# CutDown2.net
KiCad netlist of a schematic drawn in EAGLE
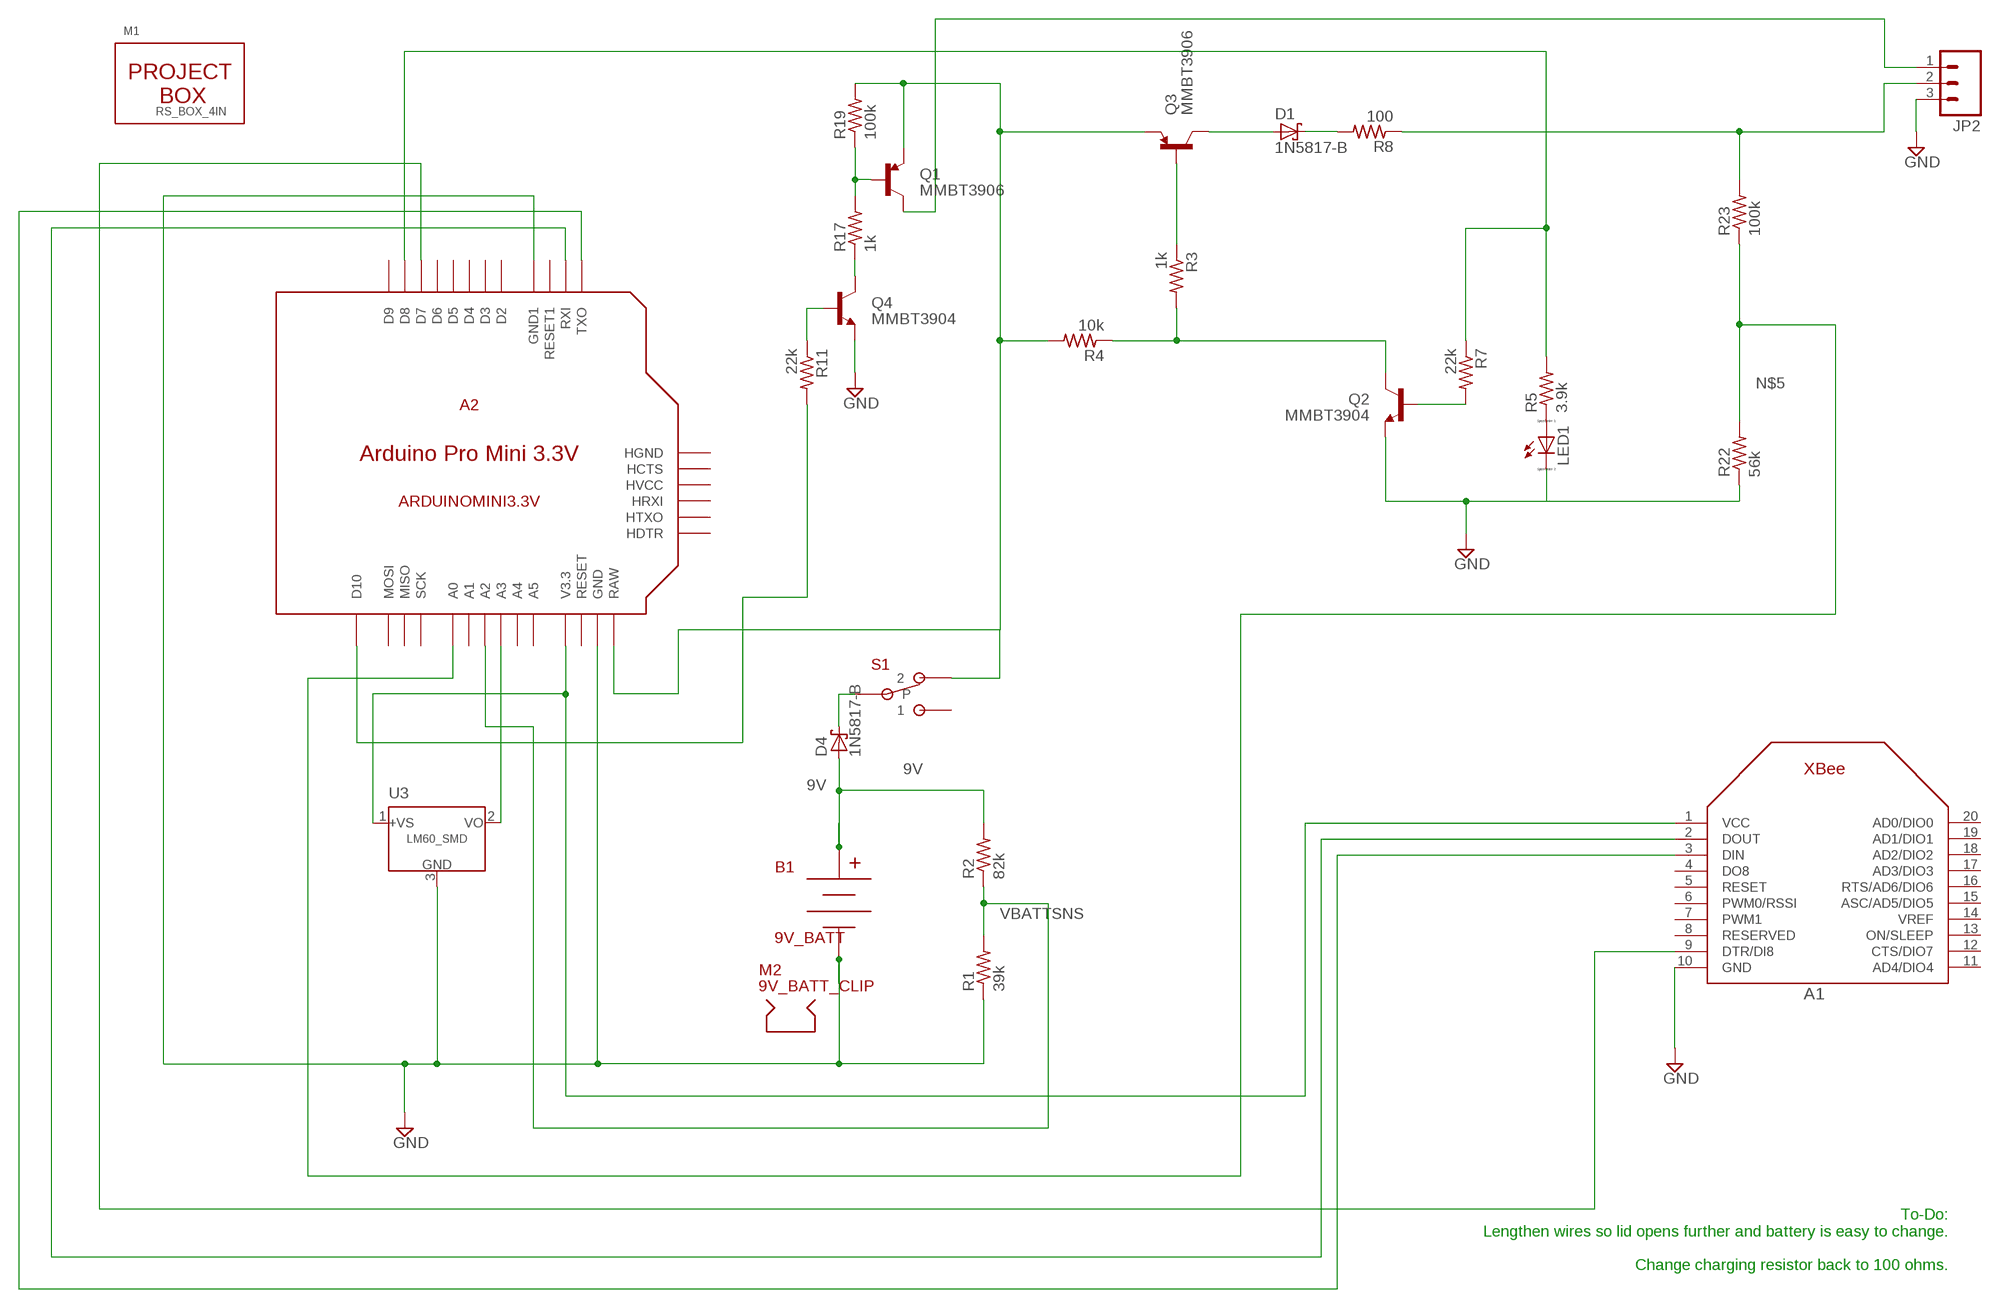
[diagram p0: schematic, sheet 1]

(export (version "E")
  (design (tool "Eeschema 10.0.6"))
  (components
    (comp (ref "A1")
      (value "XBEE")
      (footprint "eagle-import:XBEE")
      (libsource (lib "eagle-import") (part "XBEE"))
    )
    (comp (ref "A2")
      (value "ARDUINOMINI3.3V")
      (footprint "eagle-import:ARDUINOMINI3.3V")
      (libsource (lib "eagle-import") (part "ARDUINOMINI3.3V"))
    )
    (comp (ref "B1")
      (value "9V_BATT")
      (footprint "eagle-import:KEYSTONE_593_594")
      (libsource (lib "eagle-import") (part "9V_BATT"))
    )
    (comp (ref "D1")
      (value "1N5817-B")
      (footprint "eagle-import:DO41-7.6")
      (libsource (lib "eagle-import") (part "1N5817-B"))
    )
    (comp (ref "D4")
      (value "1N5817-B")
      (footprint "eagle-import:DO41-7.6")
      (libsource (lib "eagle-import") (part "1N5817-B"))
    )
    (comp (ref "JP2")
      (value "M03POLAR_LOCK")
      (footprint "eagle-import:MOLEX-1X3_LOCK")
      (libsource (lib "eagle-import") (part "M03POLAR_LOCK"))
    )
    (comp (ref "LED1")
      (value "LED_ELD260")
      (footprint "eagle-import:LED_LD260")
      (libsource (lib "eagle-import") (part "LED_ELD260"))
    )
    (comp (ref "M1")
      (value "RS_BOX_4IN")
      (footprint "eagle-import:RS_BOX_OUTLINE_4IN")
      (libsource (lib "eagle-import") (part "RS_BOX_4IN"))
    )
    (comp (ref "M2")
      (value "9V_BATT_CLIP")
      (footprint "eagle-import:KEYSTONE_9V_CLIP_H")
      (libsource (lib "eagle-import") (part "9V_BATT_CLIP"))
    )
    (comp (ref "Q1")
      (value "MMBT3906")
      (footprint "eagle-import:SOT23")
      (libsource (lib "eagle-import") (part "TRANSISTOR_PNPMMBT4403"))
    )
    (comp (ref "Q2")
      (value "MMBT3904")
      (footprint "eagle-import:SOT23")
      (libsource (lib "eagle-import") (part "TRANSISTOR_NPNSOT23"))
    )
    (comp (ref "Q3")
      (value "MMBT3906")
      (footprint "eagle-import:SOT23")
      (libsource (lib "eagle-import") (part "TRANSISTOR_PNPMMBT4403"))
    )
    (comp (ref "Q4")
      (value "MMBT3904")
      (footprint "eagle-import:SOT23")
      (libsource (lib "eagle-import") (part "TRANSISTOR_NPNSOT23"))
    )
    (comp (ref "R1")
      (value "39k")
      (footprint "eagle-import:R0805")
      (libsource (lib "eagle-import") (part "R-US_R0805"))
    )
    (comp (ref "R2")
      (value "82k")
      (footprint "eagle-import:R0805")
      (libsource (lib "eagle-import") (part "R-US_R0805"))
    )
    (comp (ref "R3")
      (value "1k")
      (footprint "eagle-import:R0805")
      (libsource (lib "eagle-import") (part "R-US_R0805"))
    )
    (comp (ref "R4")
      (value "10k")
      (footprint "eagle-import:R0805")
      (libsource (lib "eagle-import") (part "R-US_R0805"))
    )
    (comp (ref "R5")
      (value "3.9k")
      (footprint "eagle-import:R0805")
      (libsource (lib "eagle-import") (part "R-US_R0805"))
    )
    (comp (ref "R7")
      (value "22k")
      (footprint "eagle-import:R0805")
      (libsource (lib "eagle-import") (part "R-US_R0805"))
    )
    (comp (ref "R8")
      (value "100")
      (footprint "eagle-import:R0805")
      (libsource (lib "eagle-import") (part "R-US_R0805"))
    )
    (comp (ref "R11")
      (value "22k")
      (footprint "eagle-import:R0805")
      (libsource (lib "eagle-import") (part "R-US_R0805"))
    )
    (comp (ref "R17")
      (value "1k")
      (footprint "eagle-import:R0805")
      (libsource (lib "eagle-import") (part "R-US_R0805"))
    )
    (comp (ref "R19")
      (value "100k")
      (footprint "eagle-import:R0805")
      (libsource (lib "eagle-import") (part "R-US_R0805"))
    )
    (comp (ref "R22")
      (value "56k")
      (footprint "eagle-import:R0805")
      (libsource (lib "eagle-import") (part "R-US_R0805"))
    )
    (comp (ref "R23")
      (value "100k")
      (footprint "eagle-import:R0805")
      (libsource (lib "eagle-import") (part "R-US_R0805"))
    )
    (comp (ref "S1")
      (value "APEM_SPDT_25000NH")
      (footprint "eagle-import:APEM_SPDT_25000NH")
      (libsource (lib "eagle-import") (part "APEM_SPDT_25000NH"))
    )
    (comp (ref "U3")
      (value "LM60_SMD")
      (footprint "eagle-import:SOT23-3")
      (libsource (lib "eagle-import") (part "LM60_SMD"))
    )
  )
  (nets
    (net (code "1") (name "/9V") (class "Default")
      (node (ref "B1") (pin "P$1") (pinfunction "V+_P$1") (pintype "bidirectional"))
      (node (ref "B1") (pin "P$2") (pinfunction "V+_P$2") (pintype "bidirectional"))
      (node (ref "B1") (pin "P$3") (pinfunction "V+_P$3") (pintype "bidirectional"))
      (node (ref "D4") (pin "A") (pinfunction "A_A") (pintype "passive"))
      (node (ref "R2") (pin "2") (pinfunction "2_2") (pintype "passive"))
    )
    (net (code "2") (name "/N$5") (class "Default")
      (node (ref "A2") (pin "P$26") (pinfunction "A0_P$26") (pintype "bidirectional"))
      (node (ref "R22") (pin "2") (pinfunction "2_2") (pintype "passive"))
      (node (ref "R23") (pin "1") (pinfunction "1_1") (pintype "passive"))
    )
    (net (code "3") (name "/VBATTSNS") (class "Default")
      (node (ref "A2") (pin "P$24") (pinfunction "A2_P$24") (pintype "bidirectional"))
      (node (ref "R1") (pin "2") (pinfunction "2_2") (pintype "passive"))
      (node (ref "R2") (pin "1") (pinfunction "1_1") (pintype "passive"))
    )
    (net (code "4") (name "GND") (class "Default")
      (node (ref "A1") (pin "10") (pinfunction "GND_10") (pintype "power_in"))
      (node (ref "A2") (pin "P$20") (pinfunction "GND_P$20") (pintype "power_in"))
      (node (ref "A2") (pin "P$9") (pinfunction "GND1_P$9") (pintype "bidirectional"))
      (node (ref "B1") (pin "P$4") (pinfunction "V-_P$4") (pintype "bidirectional"))
      (node (ref "B1") (pin "P$5") (pinfunction "V-_P$5") (pintype "bidirectional"))
      (node (ref "B1") (pin "P$6") (pinfunction "V-_P$6") (pintype "bidirectional"))
      (node (ref "JP2") (pin "3") (pinfunction "3_3") (pintype "passive"))
      (node (ref "LED1") (pin "K") (pinfunction "C_K") (pintype "passive"))
      (node (ref "Q2") (pin "2") (pinfunction "E_2") (pintype "passive"))
      (node (ref "Q4") (pin "2") (pinfunction "E_2") (pintype "passive"))
      (node (ref "R1") (pin "1") (pinfunction "1_1") (pintype "passive"))
      (node (ref "R22") (pin "1") (pinfunction "1_1") (pintype "passive"))
      (node (ref "U3") (pin "3") (pinfunction "GND_3") (pintype "power_in"))
    )
    (net (code "5") (name "Net-(A1-DIN)") (class "Default")
      (node (ref "A1") (pin "3") (pinfunction "DIN_3") (pintype "input"))
      (node (ref "A2") (pin "P$12") (pinfunction "TXO_P$12") (pintype "bidirectional"))
    )
    (net (code "6") (name "Net-(A1-DOUT)") (class "Default")
      (node (ref "A1") (pin "2") (pinfunction "DOUT_2") (pintype "output"))
      (node (ref "A2") (pin "P$11") (pinfunction "RXI_P$11") (pintype "bidirectional"))
    )
    (net (code "7") (name "Net-(A1-DTR{slash}DI8)") (class "Default")
      (node (ref "A1") (pin "9") (pinfunction "DTR/DI8_9") (pintype "input"))
      (node (ref "A2") (pin "P$3") (pinfunction "D7_P$3") (pintype "bidirectional"))
    )
    (net (code "8") (name "Net-(A1-VCC)") (class "Default")
      (node (ref "A1") (pin "1") (pinfunction "VCC_1") (pintype "power_in"))
      (node (ref "A2") (pin "P$22") (pinfunction "V3.3_P$22") (pintype "power_in"))
      (node (ref "U3") (pin "1") (pinfunction "+VS_1") (pintype "input"))
    )
    (net (code "9") (name "Net-(A2-A3)") (class "Default")
      (node (ref "A2") (pin "P$23") (pinfunction "A3_P$23") (pintype "bidirectional"))
      (node (ref "U3") (pin "2") (pinfunction "VO_2") (pintype "input"))
    )
    (net (code "10") (name "Net-(A2-D8)") (class "Default")
      (node (ref "A2") (pin "P$2") (pinfunction "D8_P$2") (pintype "bidirectional"))
      (node (ref "R5") (pin "2") (pinfunction "2_2") (pintype "passive"))
      (node (ref "R7") (pin "1") (pinfunction "1_1") (pintype "passive"))
    )
    (net (code "11") (name "Net-(A2-D10)") (class "Default")
      (node (ref "A2") (pin "P$30") (pinfunction "D10_P$30") (pintype "bidirectional"))
      (node (ref "R11") (pin "2") (pinfunction "2_2") (pintype "passive"))
    )
    (net (code "12") (name "Net-(A2-RAW)") (class "Default")
      (node (ref "A2") (pin "P$19") (pinfunction "RAW_P$19") (pintype "bidirectional"))
      (node (ref "Q1") (pin "2") (pinfunction "E_2") (pintype "passive"))
      (node (ref "Q3") (pin "2") (pinfunction "E_2") (pintype "passive"))
      (node (ref "R19") (pin "2") (pinfunction "2_2") (pintype "passive"))
      (node (ref "R4") (pin "2") (pinfunction "2_2") (pintype "passive"))
      (node (ref "S1") (pin "P$2") (pinfunction "2_P$2") (pintype "bidirectional"))
    )
    (net (code "13") (name "Net-(D1-PadC)") (class "Default")
      (node (ref "D1") (pin "C") (pinfunction "C_C") (pintype "passive"))
      (node (ref "R8") (pin "2") (pinfunction "2_2") (pintype "passive"))
    )
    (net (code "14") (name "Net-(JP2-Pad2)") (class "Default")
      (node (ref "JP2") (pin "2") (pinfunction "2_2") (pintype "passive"))
      (node (ref "R23") (pin "2") (pinfunction "2_2") (pintype "passive"))
      (node (ref "R8") (pin "1") (pinfunction "1_1") (pintype "passive"))
    )
    (net (code "15") (name "Net-(LED1-PadA)") (class "Default")
      (node (ref "LED1") (pin "A") (pinfunction "A_A") (pintype "passive"))
      (node (ref "R5") (pin "1") (pinfunction "1_1") (pintype "passive"))
    )
    (net (code "16") (name "Net-(Q1-B)") (class "Default")
      (node (ref "Q1") (pin "1") (pinfunction "B_1") (pintype "passive"))
      (node (ref "R17") (pin "2") (pinfunction "2_2") (pintype "passive"))
      (node (ref "R19") (pin "1") (pinfunction "1_1") (pintype "passive"))
    )
    (net (code "17") (name "Net-(Q1-C)") (class "Default")
      (node (ref "JP2") (pin "1") (pinfunction "1_1") (pintype "passive"))
      (node (ref "Q1") (pin "3") (pinfunction "C_3") (pintype "passive"))
    )
    (net (code "18") (name "Net-(Q2-B)") (class "Default")
      (node (ref "Q2") (pin "1") (pinfunction "B_1") (pintype "passive"))
      (node (ref "R7") (pin "2") (pinfunction "2_2") (pintype "passive"))
    )
    (net (code "19") (name "Net-(Q2-C)") (class "Default")
      (node (ref "Q2") (pin "3") (pinfunction "C_3") (pintype "passive"))
      (node (ref "R3") (pin "2") (pinfunction "2_2") (pintype "passive"))
      (node (ref "R4") (pin "1") (pinfunction "1_1") (pintype "passive"))
    )
    (net (code "20") (name "Net-(Q3-B)") (class "Default")
      (node (ref "Q3") (pin "1") (pinfunction "B_1") (pintype "passive"))
      (node (ref "R3") (pin "1") (pinfunction "1_1") (pintype "passive"))
    )
    (net (code "21") (name "Net-(Q3-C)") (class "Default")
      (node (ref "D1") (pin "A") (pinfunction "A_A") (pintype "passive"))
      (node (ref "Q3") (pin "3") (pinfunction "C_3") (pintype "passive"))
    )
    (net (code "22") (name "Net-(Q4-B)") (class "Default")
      (node (ref "Q4") (pin "1") (pinfunction "B_1") (pintype "passive"))
      (node (ref "R11") (pin "1") (pinfunction "1_1") (pintype "passive"))
    )
    (net (code "23") (name "Net-(Q4-C)") (class "Default")
      (node (ref "Q4") (pin "3") (pinfunction "C_3") (pintype "passive"))
      (node (ref "R17") (pin "1") (pinfunction "1_1") (pintype "passive"))
    )
    (net (code "24") (name "Net-(S1-P)") (class "Default")
      (node (ref "D4") (pin "C") (pinfunction "C_C") (pintype "passive"))
      (node (ref "S1") (pin "P$3") (pinfunction "P_P$3") (pintype "bidirectional"))
    )
    (net (code "25") (name "unconnected-(A1-AD0{slash}DIO0-Pad20)") (class "Default")
      (node (ref "A1") (pin "20") (pinfunction "AD0/DIO0_20") (pintype "bidirectional"))
    )
    (net (code "26") (name "unconnected-(A1-AD1{slash}DIO1-Pad19)") (class "Default")
      (node (ref "A1") (pin "19") (pinfunction "AD1/DIO1_19") (pintype "bidirectional"))
    )
    (net (code "27") (name "unconnected-(A1-AD2{slash}DIO2-Pad18)") (class "Default")
      (node (ref "A1") (pin "18") (pinfunction "AD2/DIO2_18") (pintype "bidirectional"))
    )
    (net (code "28") (name "unconnected-(A1-AD3{slash}DIO3-Pad17)") (class "Default")
      (node (ref "A1") (pin "17") (pinfunction "AD3/DIO3_17") (pintype "bidirectional"))
    )
    (net (code "29") (name "unconnected-(A1-AD4{slash}DIO4-Pad11)") (class "Default")
      (node (ref "A1") (pin "11") (pinfunction "AD4/DIO4_11") (pintype "bidirectional"))
    )
    (net (code "30") (name "unconnected-(A1-ASC{slash}AD5{slash}DIO5-Pad15)") (class "Default")
      (node (ref "A1") (pin "15") (pinfunction "ASC/AD5/DIO5_15") (pintype "bidirectional"))
    )
    (net (code "31") (name "unconnected-(A1-CTS{slash}DIO7-Pad12)") (class "Default")
      (node (ref "A1") (pin "12") (pinfunction "CTS/DIO7_12") (pintype "bidirectional"))
    )
    (net (code "32") (name "unconnected-(A1-DO8-Pad4)") (class "Default")
      (node (ref "A1") (pin "4") (pinfunction "DO8_4") (pintype "output"))
    )
    (net (code "33") (name "unconnected-(A1-ON{slash}SLEEP-Pad13)") (class "Default")
      (node (ref "A1") (pin "13") (pinfunction "ON/SLEEP_13") (pintype "output"))
    )
    (net (code "34") (name "unconnected-(A1-PWM0{slash}RSSI-Pad6)") (class "Default")
      (node (ref "A1") (pin "6") (pinfunction "PWM0/RSSI_6") (pintype "output"))
    )
    (net (code "35") (name "unconnected-(A1-PWM1-Pad7)") (class "Default")
      (node (ref "A1") (pin "7") (pinfunction "PWM1_7") (pintype "output"))
    )
    (net (code "36") (name "unconnected-(A1-RESERVED-Pad8)") (class "Default")
      (node (ref "A1") (pin "8") (pinfunction "RESERVED_8") (pintype "no_connect"))
    )
    (net (code "37") (name "unconnected-(A1-RESET-Pad5)") (class "Default")
      (node (ref "A1") (pin "5") (pinfunction "RESET_5") (pintype "input"))
    )
    (net (code "38") (name "unconnected-(A1-RTS{slash}AD6{slash}DIO6-Pad16)") (class "Default")
      (node (ref "A1") (pin "16") (pinfunction "RTS/AD6/DIO6_16") (pintype "bidirectional"))
    )
    (net (code "39") (name "unconnected-(A1-VREF-Pad14)") (class "Default")
      (node (ref "A1") (pin "14") (pinfunction "VREF_14") (pintype "input"))
    )
    (net (code "40") (name "unconnected-(A2-A1-PadP$25)") (class "Default")
      (node (ref "A2") (pin "P$25") (pinfunction "A1_P$25") (pintype "bidirectional"))
    )
    (net (code "41") (name "unconnected-(A2-A4-PadP$35)") (class "Default")
      (node (ref "A2") (pin "P$35") (pinfunction "A4_P$35") (pintype "bidirectional"))
    )
    (net (code "42") (name "unconnected-(A2-A5-PadP$34)") (class "Default")
      (node (ref "A2") (pin "P$34") (pinfunction "A5_P$34") (pintype "bidirectional"))
    )
    (net (code "43") (name "unconnected-(A2-D2-PadP$8)") (class "Default")
      (node (ref "A2") (pin "P$8") (pinfunction "D2_P$8") (pintype "bidirectional"))
    )
    (net (code "44") (name "unconnected-(A2-D3-PadP$7)") (class "Default")
      (node (ref "A2") (pin "P$7") (pinfunction "D3_P$7") (pintype "bidirectional"))
    )
    (net (code "45") (name "unconnected-(A2-D4-PadP$6)") (class "Default")
      (node (ref "A2") (pin "P$6") (pinfunction "D4_P$6") (pintype "bidirectional"))
    )
    (net (code "46") (name "unconnected-(A2-D5-PadP$5)") (class "Default")
      (node (ref "A2") (pin "P$5") (pinfunction "D5_P$5") (pintype "bidirectional"))
    )
    (net (code "47") (name "unconnected-(A2-D6-PadP$4)") (class "Default")
      (node (ref "A2") (pin "P$4") (pinfunction "D6_P$4") (pintype "bidirectional"))
    )
    (net (code "48") (name "unconnected-(A2-D9-PadP$1)") (class "Default")
      (node (ref "A2") (pin "P$1") (pinfunction "D9_P$1") (pintype "bidirectional"))
    )
    (net (code "49") (name "unconnected-(A2-HCTS-PadP$14)") (class "Default")
      (node (ref "A2") (pin "P$14") (pinfunction "HCTS_P$14") (pintype "bidirectional"))
    )
    (net (code "50") (name "unconnected-(A2-HDTR-PadP$18)") (class "Default")
      (node (ref "A2") (pin "P$18") (pinfunction "HDTR_P$18") (pintype "bidirectional"))
    )
    (net (code "51") (name "unconnected-(A2-HGND-PadP$13)") (class "Default")
      (node (ref "A2") (pin "P$13") (pinfunction "HGND_P$13") (pintype "bidirectional"))
    )
    (net (code "52") (name "unconnected-(A2-HRXI-PadP$16)") (class "Default")
      (node (ref "A2") (pin "P$16") (pinfunction "HRXI_P$16") (pintype "bidirectional"))
    )
    (net (code "53") (name "unconnected-(A2-HTXO-PadP$17)") (class "Default")
      (node (ref "A2") (pin "P$17") (pinfunction "HTXO_P$17") (pintype "bidirectional"))
    )
    (net (code "54") (name "unconnected-(A2-HVCC-PadP$15)") (class "Default")
      (node (ref "A2") (pin "P$15") (pinfunction "HVCC_P$15") (pintype "bidirectional"))
    )
    (net (code "55") (name "unconnected-(A2-MISO-PadP$28)") (class "Default")
      (node (ref "A2") (pin "P$28") (pinfunction "MISO_P$28") (pintype "bidirectional"))
    )
    (net (code "56") (name "unconnected-(A2-MOSI-PadP$29)") (class "Default")
      (node (ref "A2") (pin "P$29") (pinfunction "MOSI_P$29") (pintype "bidirectional"))
    )
    (net (code "57") (name "unconnected-(A2-RESET-PadP$21)") (class "Default")
      (node (ref "A2") (pin "P$21") (pinfunction "RESET_P$21") (pintype "bidirectional"))
    )
    (net (code "58") (name "unconnected-(A2-RESET1-PadP$10)") (class "Default")
      (node (ref "A2") (pin "P$10") (pinfunction "RESET1_P$10") (pintype "bidirectional"))
    )
    (net (code "59") (name "unconnected-(A2-SCK-PadP$27)") (class "Default")
      (node (ref "A2") (pin "P$27") (pinfunction "SCK_P$27") (pintype "bidirectional"))
    )
    (net (code "60") (name "unconnected-(S1-1-PadP$1)") (class "Default")
      (node (ref "S1") (pin "P$1") (pinfunction "1_P$1") (pintype "bidirectional"))
    )
  )
)
